# sirius1_trs80_model_2.net
KiCad netlist of a schematic drawn in EAGLE
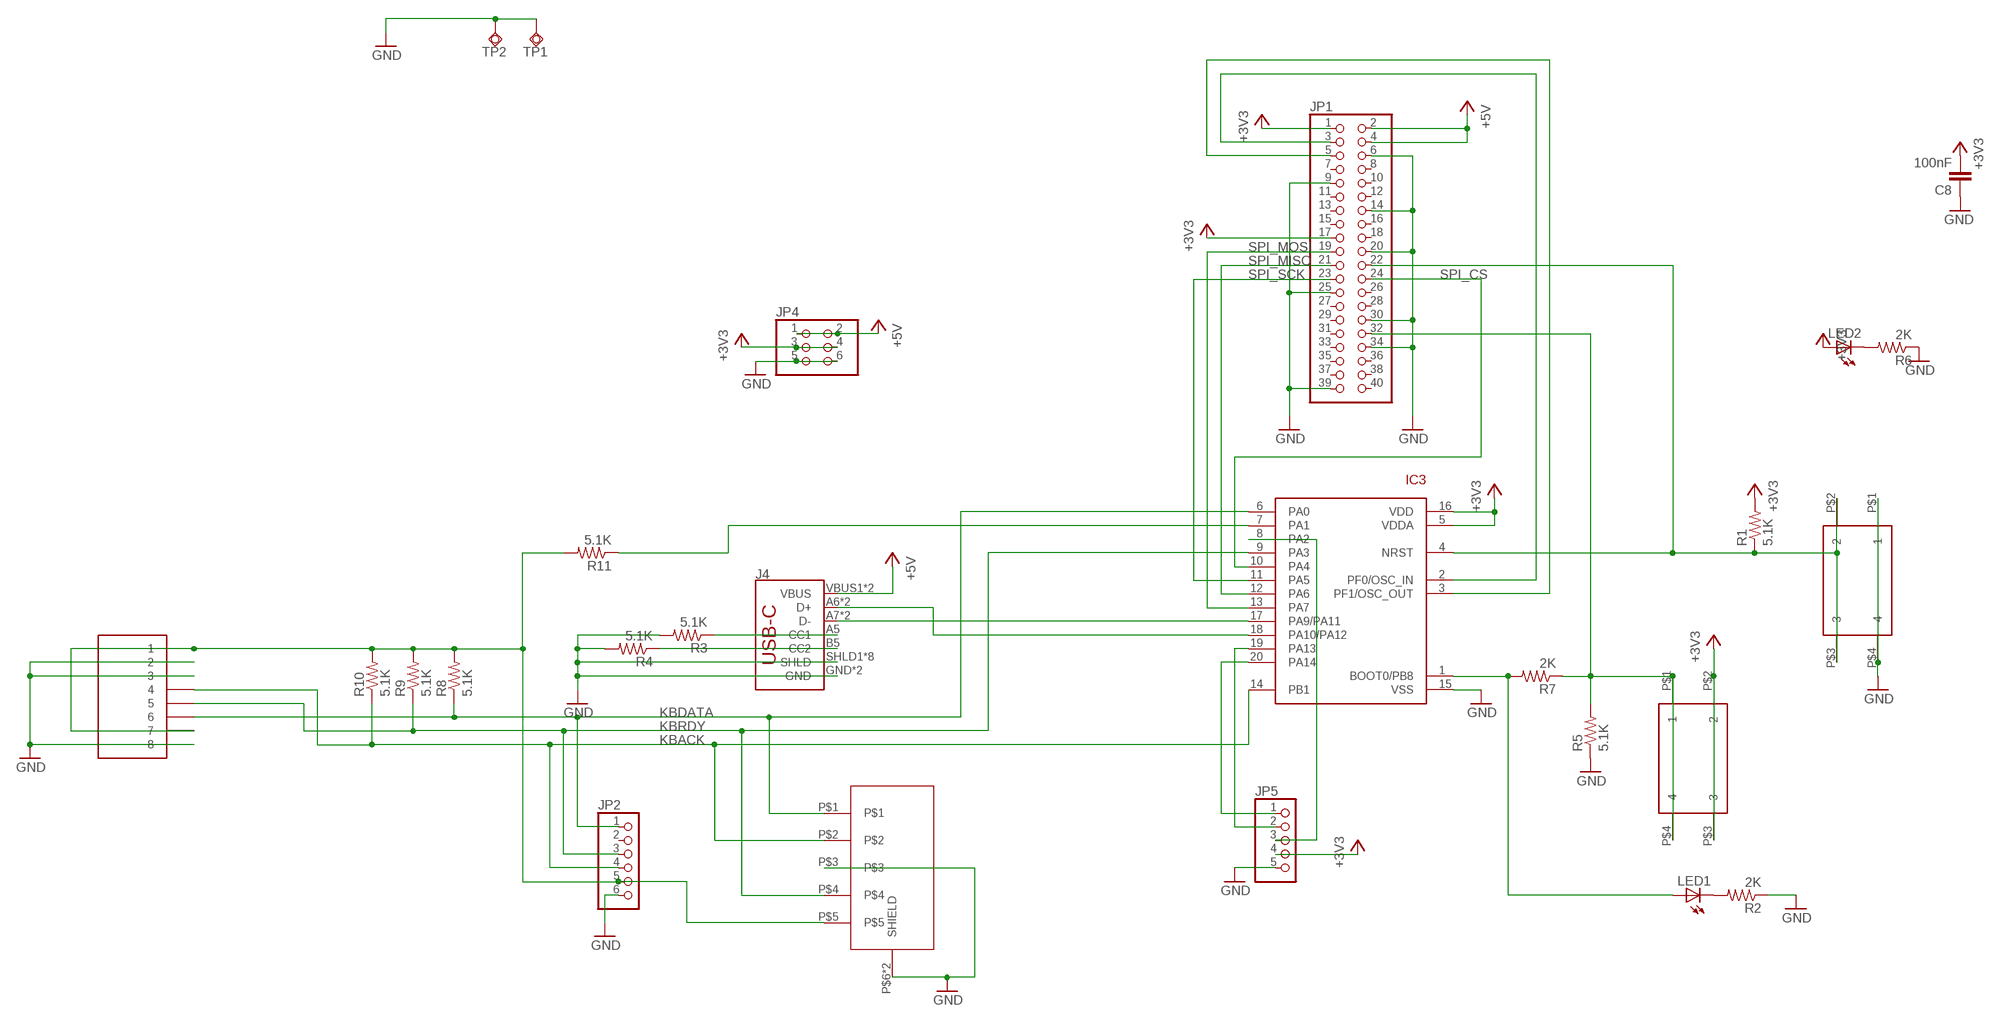
[diagram p0: schematic, sheet 1, part 1 of 2]
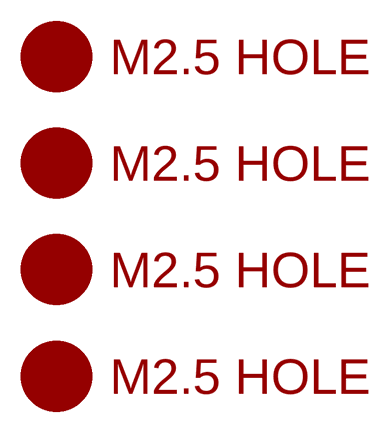
[diagram p1: schematic, sheet 1, part 2 of 2]

(export (version "E")
  (design (tool "Eeschema 10.0.6"))
  (components
    (comp (ref "C8")
      (value "100nF")
      (footprint "eagle-import:0805@1")
      (libsource (lib "eagle-import") (part "CAP0805"))
    )
    (comp (ref "IC3")
      (value "STM32F042F4")
      (footprint "eagle-import:TSSOP20")
      (libsource (lib "eagle-import") (part "STM32F042F4"))
    )
    (comp (ref "J4")
      (value "USB_C16PIN")
      (footprint "eagle-import:USB-C-16P")
      (libsource (lib "eagle-import") (part "USB_C16PIN"))
    )
    (comp (ref "JP1")
      (value "PINHD-2X20-BIG")
      (footprint "eagle-import:2X20-BIG")
      (libsource (lib "eagle-import") (part "PINHD-2X20-BIG"))
    )
    (comp (ref "JP2")
      (value "PINHD-1X6")
      (footprint "eagle-import:1X06")
      (libsource (lib "eagle-import") (part "PINHD-1X6"))
    )
    (comp (ref "JP4")
      (value "PINHD-2X3")
      (footprint "eagle-import:2X03")
      (libsource (lib "eagle-import") (part "PINHD-2X3"))
    )
    (comp (ref "JP5")
      (value "PINHD-1X5")
      (footprint "eagle-import:1X05")
      (libsource (lib "eagle-import") (part "PINHD-1X5"))
    )
    (comp (ref "LED1")
      (value "LEDCHIP-LED0805")
      (footprint "eagle-import:CHIP-LED0805")
      (libsource (lib "eagle-import") (part "LEDCHIP-LED0805"))
    )
    (comp (ref "LED2")
      (value "LEDCHIP-LED0805")
      (footprint "eagle-import:CHIP-LED0805")
      (libsource (lib "eagle-import") (part "LEDCHIP-LED0805"))
    )
    (comp (ref "R1")
      (value "5.1K")
      (footprint "eagle-import:0805")
      (libsource (lib "eagle-import") (part "RESISTOR0805-RES"))
    )
    (comp (ref "R2")
      (value "2K")
      (footprint "eagle-import:0805")
      (libsource (lib "eagle-import") (part "RESISTOR0805-RES"))
    )
    (comp (ref "R3")
      (value "5.1K")
      (footprint "eagle-import:0805")
      (libsource (lib "eagle-import") (part "RESISTOR0805-RES"))
    )
    (comp (ref "R4")
      (value "5.1K")
      (footprint "eagle-import:0805")
      (libsource (lib "eagle-import") (part "RESISTOR0805-RES"))
    )
    (comp (ref "R5")
      (value "5.1K")
      (footprint "eagle-import:0805")
      (libsource (lib "eagle-import") (part "RESISTOR0805-RES"))
    )
    (comp (ref "R6")
      (value "2K")
      (footprint "eagle-import:0805")
      (libsource (lib "eagle-import") (part "RESISTOR0805-RES"))
    )
    (comp (ref "R7")
      (value "2K")
      (footprint "eagle-import:0805")
      (libsource (lib "eagle-import") (part "RESISTOR0805-RES"))
    )
    (comp (ref "R8")
      (value "5.1K")
      (footprint "eagle-import:0805")
      (libsource (lib "eagle-import") (part "RESISTOR0805-RES"))
    )
    (comp (ref "R9")
      (value "5.1K")
      (footprint "eagle-import:0805")
      (libsource (lib "eagle-import") (part "RESISTOR0805-RES"))
    )
    (comp (ref "R10")
      (value "5.1K")
      (footprint "eagle-import:0805")
      (libsource (lib "eagle-import") (part "RESISTOR0805-RES"))
    )
    (comp (ref "R11")
      (value "5.1K")
      (footprint "eagle-import:0805")
      (libsource (lib "eagle-import") (part "RESISTOR0805-RES"))
    )
    (comp (ref "SW1")
      (value "324_SW")
      (footprint "eagle-import:342_SWICH_FOOT")
      (libsource (lib "eagle-import") (part "324_SW"))
    )
    (comp (ref "SW4")
      (value "324_SW")
      (footprint "eagle-import:342_SWICH_FOOT")
      (libsource (lib "eagle-import") (part "324_SW"))
    )
    (comp (ref "TP1")
      (value "TPSQPAD1-17")
      (footprint "eagle-import:P1-17")
      (libsource (lib "eagle-import") (part "TPSQPAD1-17"))
    )
    (comp (ref "TP2")
      (value "TPSQPAD1-17")
      (footprint "eagle-import:P1-17")
      (libsource (lib "eagle-import") (part "TPSQPAD1-17"))
    )
    (comp (ref "U$1")
      (value "DIN5")
      (footprint "eagle-import:DIN5")
      (libsource (lib "eagle-import") (part "DIN5"))
    )
    (comp (ref "U$2")
      (value "M2.5HOLE")
      (footprint "eagle-import:M2.5HOLE")
      (libsource (lib "eagle-import") (part "M2.5HOLE"))
    )
    (comp (ref "U$3")
      (value "M2.5HOLE")
      (footprint "eagle-import:M2.5HOLE")
      (libsource (lib "eagle-import") (part "M2.5HOLE"))
    )
    (comp (ref "U$4")
      (value "M2.5HOLE")
      (footprint "eagle-import:M2.5HOLE")
      (libsource (lib "eagle-import") (part "M2.5HOLE"))
    )
    (comp (ref "U$5")
      (value "M2.5HOLE")
      (footprint "eagle-import:M2.5HOLE")
      (libsource (lib "eagle-import") (part "M2.5HOLE"))
    )
    (comp (ref "U1")
      (value "RJ45")
      (footprint "eagle-import:RJ45-8")
      (libsource (lib "eagle-import") (part "RJ45-8PTH"))
    )
  )
  (nets
    (net (code "1") (name "+3V3") (class "Default")
      (node (ref "C8") (pin "2") (pinfunction "2_2") (pintype "passive"))
      (node (ref "IC3") (pin "16") (pinfunction "VDD_16") (pintype "bidirectional"))
      (node (ref "IC3") (pin "5") (pinfunction "VDDA_5") (pintype "bidirectional"))
      (node (ref "JP1") (pin "1") (pinfunction "1_1") (pintype "passive"))
      (node (ref "JP1") (pin "17") (pinfunction "17_17") (pintype "passive"))
      (node (ref "JP4") (pin "3") (pinfunction "3_3") (pintype "passive"))
      (node (ref "JP4") (pin "4") (pinfunction "4_4") (pintype "passive"))
      (node (ref "JP5") (pin "4") (pinfunction "4_4") (pintype "passive"))
      (node (ref "LED2") (pin "A") (pinfunction "A_A") (pintype "passive"))
      (node (ref "R1") (pin "2") (pinfunction "2_2") (pintype "passive"))
      (node (ref "SW1") (pin "P$2") (pinfunction "2_P$2") (pintype "bidirectional"))
      (node (ref "SW1") (pin "P$3") (pinfunction "3_P$3") (pintype "bidirectional"))
    )
    (net (code "2") (name "+5V") (class "Default")
      (node (ref "J4") (pin "VBUS1") (pinfunction "VBUS_VBUS1") (pintype "bidirectional"))
      (node (ref "J4") (pin "VBUS2") (pinfunction "VBUS_VBUS2") (pintype "bidirectional"))
      (node (ref "JP1") (pin "2") (pinfunction "2_2") (pintype "passive"))
      (node (ref "JP1") (pin "4") (pinfunction "4_4") (pintype "passive"))
      (node (ref "JP4") (pin "1") (pinfunction "1_1") (pintype "passive"))
      (node (ref "JP4") (pin "2") (pinfunction "2_2") (pintype "passive"))
    )
    (net (code "3") (name "/KBACK") (class "Default")
      (node (ref "IC3") (pin "14") (pinfunction "PB1_14") (pintype "bidirectional"))
      (node (ref "JP2") (pin "4") (pinfunction "4_4") (pintype "passive"))
      (node (ref "R10") (pin "1") (pinfunction "1_1") (pintype "passive"))
      (node (ref "U$1") (pin "P$2") (pinfunction "P$2_P$2") (pintype "bidirectional"))
      (node (ref "U1") (pin "4") (pinfunction "4_4") (pintype "bidirectional"))
    )
    (net (code "4") (name "/KBDATA") (class "Default")
      (node (ref "IC3") (pin "6") (pinfunction "PA0_6") (pintype "bidirectional"))
      (node (ref "JP2") (pin "1") (pinfunction "1_1") (pintype "passive"))
      (node (ref "R8") (pin "1") (pinfunction "1_1") (pintype "passive"))
      (node (ref "U$1") (pin "P$1") (pinfunction "P$1_P$1") (pintype "bidirectional"))
      (node (ref "U1") (pin "6") (pinfunction "6_6") (pintype "bidirectional"))
    )
    (net (code "5") (name "/KBRDY") (class "Default")
      (node (ref "IC3") (pin "9") (pinfunction "PA3_9") (pintype "bidirectional"))
      (node (ref "JP2") (pin "3") (pinfunction "3_3") (pintype "passive"))
      (node (ref "R9") (pin "1") (pinfunction "1_1") (pintype "passive"))
      (node (ref "U$1") (pin "P$4") (pinfunction "P$4_P$4") (pintype "bidirectional"))
      (node (ref "U1") (pin "5") (pinfunction "5_5") (pintype "bidirectional"))
    )
    (net (code "6") (name "/SPI_CS") (class "Default")
      (node (ref "IC3") (pin "10") (pinfunction "PA4_10") (pintype "bidirectional"))
      (node (ref "JP1") (pin "24") (pinfunction "24_24") (pintype "passive"))
    )
    (net (code "7") (name "/SPI_MISO") (class "Default")
      (node (ref "IC3") (pin "12") (pinfunction "PA6_12") (pintype "bidirectional"))
      (node (ref "JP1") (pin "21") (pinfunction "21_21") (pintype "passive"))
    )
    (net (code "8") (name "/SPI_MOSI") (class "Default")
      (node (ref "IC3") (pin "13") (pinfunction "PA7_13") (pintype "bidirectional"))
      (node (ref "JP1") (pin "19") (pinfunction "19_19") (pintype "passive"))
    )
    (net (code "9") (name "/SPI_SCK") (class "Default")
      (node (ref "IC3") (pin "11") (pinfunction "PA5_11") (pintype "bidirectional"))
      (node (ref "JP1") (pin "23") (pinfunction "23_23") (pintype "passive"))
    )
    (net (code "10") (name "GND") (class "Default")
      (node (ref "C8") (pin "1") (pinfunction "1_1") (pintype "passive"))
      (node (ref "IC3") (pin "15") (pinfunction "VSS_15") (pintype "bidirectional"))
      (node (ref "J4") (pin "GND") (pinfunction "GND_GND") (pintype "bidirectional"))
      (node (ref "J4") (pin "GND2") (pinfunction "GND_GND2") (pintype "bidirectional"))
      (node (ref "J4") (pin "SHLD1") (pinfunction "SHLD_SHLD1") (pintype "bidirectional"))
      (node (ref "J4") (pin "SHLD2") (pinfunction "SHLD_SHLD2") (pintype "bidirectional"))
      (node (ref "J4") (pin "SHLD3") (pinfunction "SHLD_SHLD3") (pintype "bidirectional"))
      (node (ref "J4") (pin "SHLD4") (pinfunction "SHLD_SHLD4") (pintype "bidirectional"))
      (node (ref "J4") (pin "SHLD5") (pinfunction "SHLD_SHLD5") (pintype "bidirectional"))
      (node (ref "J4") (pin "SHLD6") (pinfunction "SHLD_SHLD6") (pintype "bidirectional"))
      (node (ref "J4") (pin "SHLD7") (pinfunction "SHLD_SHLD7") (pintype "bidirectional"))
      (node (ref "J4") (pin "SHLD8") (pinfunction "SHLD_SHLD8") (pintype "bidirectional"))
      (node (ref "JP1") (pin "14") (pinfunction "14_14") (pintype "passive"))
      (node (ref "JP1") (pin "20") (pinfunction "20_20") (pintype "passive"))
      (node (ref "JP1") (pin "25") (pinfunction "25_25") (pintype "passive"))
      (node (ref "JP1") (pin "30") (pinfunction "30_30") (pintype "passive"))
      (node (ref "JP1") (pin "34") (pinfunction "34_34") (pintype "passive"))
      (node (ref "JP1") (pin "39") (pinfunction "39_39") (pintype "passive"))
      (node (ref "JP1") (pin "6") (pinfunction "6_6") (pintype "passive"))
      (node (ref "JP1") (pin "9") (pinfunction "9_9") (pintype "passive"))
      (node (ref "JP2") (pin "6") (pinfunction "6_6") (pintype "passive"))
      (node (ref "JP4") (pin "5") (pinfunction "5_5") (pintype "passive"))
      (node (ref "JP4") (pin "6") (pinfunction "6_6") (pintype "passive"))
      (node (ref "JP5") (pin "5") (pinfunction "5_5") (pintype "passive"))
      (node (ref "R2") (pin "1") (pinfunction "1_1") (pintype "passive"))
      (node (ref "R3") (pin "2") (pinfunction "2_2") (pintype "passive"))
      (node (ref "R4") (pin "2") (pinfunction "2_2") (pintype "passive"))
      (node (ref "R5") (pin "1") (pinfunction "1_1") (pintype "passive"))
      (node (ref "R6") (pin "1") (pinfunction "1_1") (pintype "passive"))
      (node (ref "SW4") (pin "P$1") (pinfunction "1_P$1") (pintype "bidirectional"))
      (node (ref "SW4") (pin "P$4") (pinfunction "4_P$4") (pintype "bidirectional"))
      (node (ref "TP1") (pin "TP") (pinfunction "TP_TP") (pintype "input"))
      (node (ref "TP2") (pin "TP") (pinfunction "TP_TP") (pintype "input"))
      (node (ref "U$1") (pin "P$3") (pinfunction "P$3_P$3") (pintype "bidirectional"))
      (node (ref "U$1") (pin "P$6") (pinfunction "SHIELD_P$6") (pintype "bidirectional"))
      (node (ref "U$1") (pin "P$7") (pinfunction "SHIELD_P$7") (pintype "bidirectional"))
      (node (ref "U1") (pin "2") (pinfunction "2_2") (pintype "bidirectional"))
      (node (ref "U1") (pin "3") (pinfunction "3_3") (pintype "bidirectional"))
      (node (ref "U1") (pin "8") (pinfunction "8_8") (pintype "bidirectional"))
    )
    (net (code "11") (name "Net-(IC3-BOOT0{slash}PB8)") (class "Default")
      (node (ref "IC3") (pin "1") (pinfunction "BOOT0/PB8_1") (pintype "bidirectional"))
      (node (ref "LED1") (pin "A") (pinfunction "A_A") (pintype "passive"))
      (node (ref "R7") (pin "2") (pinfunction "2_2") (pintype "passive"))
    )
    (net (code "12") (name "Net-(IC3-NRST)") (class "Default")
      (node (ref "IC3") (pin "4") (pinfunction "NRST_4") (pintype "bidirectional"))
      (node (ref "JP1") (pin "22") (pinfunction "22_22") (pintype "passive"))
      (node (ref "R1") (pin "1") (pinfunction "1_1") (pintype "passive"))
      (node (ref "SW4") (pin "P$2") (pinfunction "2_P$2") (pintype "bidirectional"))
      (node (ref "SW4") (pin "P$3") (pinfunction "3_P$3") (pintype "bidirectional"))
    )
    (net (code "13") (name "Net-(IC3-PA1)") (class "Default")
      (node (ref "IC3") (pin "7") (pinfunction "PA1_7") (pintype "bidirectional"))
      (node (ref "R11") (pin "1") (pinfunction "1_1") (pintype "passive"))
    )
    (net (code "14") (name "Net-(IC3-PA2)") (class "Default")
      (node (ref "IC3") (pin "8") (pinfunction "PA2_8") (pintype "bidirectional"))
      (node (ref "JP5") (pin "3") (pinfunction "3_3") (pintype "passive"))
    )
    (net (code "15") (name "Net-(IC3-PA9{slash}PA11)") (class "Default")
      (node (ref "IC3") (pin "17") (pinfunction "PA9/PA11_17") (pintype "bidirectional"))
      (node (ref "J4") (pin "A7") (pinfunction "D-_A7") (pintype "bidirectional"))
      (node (ref "J4") (pin "B7") (pinfunction "D-_B7") (pintype "bidirectional"))
    )
    (net (code "16") (name "Net-(IC3-PA10{slash}PA12)") (class "Default")
      (node (ref "IC3") (pin "18") (pinfunction "PA10/PA12_18") (pintype "bidirectional"))
      (node (ref "J4") (pin "A6") (pinfunction "D+_A6") (pintype "bidirectional"))
      (node (ref "J4") (pin "B6") (pinfunction "D+_B6") (pintype "bidirectional"))
    )
    (net (code "17") (name "Net-(IC3-PA13)") (class "Default")
      (node (ref "IC3") (pin "19") (pinfunction "PA13_19") (pintype "bidirectional"))
      (node (ref "JP5") (pin "2") (pinfunction "2_2") (pintype "passive"))
    )
    (net (code "18") (name "Net-(IC3-PA14)") (class "Default")
      (node (ref "IC3") (pin "20") (pinfunction "PA14_20") (pintype "bidirectional"))
      (node (ref "JP5") (pin "1") (pinfunction "1_1") (pintype "passive"))
    )
    (net (code "19") (name "Net-(IC3-PF0{slash}OSC_IN)") (class "Default")
      (node (ref "IC3") (pin "2") (pinfunction "PF0/OSC_IN_2") (pintype "bidirectional"))
      (node (ref "JP1") (pin "3") (pinfunction "3_3") (pintype "passive"))
    )
    (net (code "20") (name "Net-(IC3-PF1{slash}OSC_OUT)") (class "Default")
      (node (ref "IC3") (pin "3") (pinfunction "PF1/OSC_OUT_3") (pintype "bidirectional"))
      (node (ref "JP1") (pin "5") (pinfunction "5_5") (pintype "passive"))
    )
    (net (code "21") (name "Net-(J4-CC1)") (class "Default")
      (node (ref "J4") (pin "A5") (pinfunction "CC1_A5") (pintype "bidirectional"))
      (node (ref "R3") (pin "1") (pinfunction "1_1") (pintype "passive"))
    )
    (net (code "22") (name "Net-(J4-CC2)") (class "Default")
      (node (ref "J4") (pin "B5") (pinfunction "CC2_B5") (pintype "bidirectional"))
      (node (ref "R4") (pin "1") (pinfunction "1_1") (pintype "passive"))
    )
    (net (code "23") (name "Net-(JP2-Pad5)") (class "Default")
      (node (ref "JP2") (pin "5") (pinfunction "5_5") (pintype "passive"))
      (node (ref "R10") (pin "2") (pinfunction "2_2") (pintype "passive"))
      (node (ref "R11") (pin "2") (pinfunction "2_2") (pintype "passive"))
      (node (ref "R8") (pin "2") (pinfunction "2_2") (pintype "passive"))
      (node (ref "R9") (pin "2") (pinfunction "2_2") (pintype "passive"))
      (node (ref "U$1") (pin "P$5") (pinfunction "P$5_P$5") (pintype "bidirectional"))
      (node (ref "U1") (pin "1") (pinfunction "1_1") (pintype "bidirectional"))
      (node (ref "U1") (pin "7") (pinfunction "7_7") (pintype "bidirectional"))
    )
    (net (code "24") (name "Net-(LED1-PadC)") (class "Default")
      (node (ref "LED1") (pin "C") (pinfunction "C_C") (pintype "passive"))
      (node (ref "R2") (pin "2") (pinfunction "2_2") (pintype "passive"))
    )
    (net (code "25") (name "Net-(LED2-PadC)") (class "Default")
      (node (ref "LED2") (pin "C") (pinfunction "C_C") (pintype "passive"))
      (node (ref "R6") (pin "2") (pinfunction "2_2") (pintype "passive"))
    )
    (net (code "26") (name "Net-(SW1-1)") (class "Default")
      (node (ref "JP1") (pin "32") (pinfunction "32_32") (pintype "passive"))
      (node (ref "R5") (pin "2") (pinfunction "2_2") (pintype "passive"))
      (node (ref "R7") (pin "1") (pinfunction "1_1") (pintype "passive"))
      (node (ref "SW1") (pin "P$1") (pinfunction "1_P$1") (pintype "bidirectional"))
      (node (ref "SW1") (pin "P$4") (pinfunction "4_P$4") (pintype "bidirectional"))
    )
    (net (code "27") (name "unconnected-(JP1-Pad7)") (class "Default")
      (node (ref "JP1") (pin "7") (pinfunction "7_7") (pintype "passive"))
    )
    (net (code "28") (name "unconnected-(JP1-Pad8)") (class "Default")
      (node (ref "JP1") (pin "8") (pinfunction "8_8") (pintype "passive"))
    )
    (net (code "29") (name "unconnected-(JP1-Pad10)") (class "Default")
      (node (ref "JP1") (pin "10") (pinfunction "10_10") (pintype "passive"))
    )
    (net (code "30") (name "unconnected-(JP1-Pad11)") (class "Default")
      (node (ref "JP1") (pin "11") (pinfunction "11_11") (pintype "passive"))
    )
    (net (code "31") (name "unconnected-(JP1-Pad12)") (class "Default")
      (node (ref "JP1") (pin "12") (pinfunction "12_12") (pintype "passive"))
    )
    (net (code "32") (name "unconnected-(JP1-Pad13)") (class "Default")
      (node (ref "JP1") (pin "13") (pinfunction "13_13") (pintype "passive"))
    )
    (net (code "33") (name "unconnected-(JP1-Pad15)") (class "Default")
      (node (ref "JP1") (pin "15") (pinfunction "15_15") (pintype "passive"))
    )
    (net (code "34") (name "unconnected-(JP1-Pad16)") (class "Default")
      (node (ref "JP1") (pin "16") (pinfunction "16_16") (pintype "passive"))
    )
    (net (code "35") (name "unconnected-(JP1-Pad18)") (class "Default")
      (node (ref "JP1") (pin "18") (pinfunction "18_18") (pintype "passive"))
    )
    (net (code "36") (name "unconnected-(JP1-Pad26)") (class "Default")
      (node (ref "JP1") (pin "26") (pinfunction "26_26") (pintype "passive"))
    )
    (net (code "37") (name "unconnected-(JP1-Pad27)") (class "Default")
      (node (ref "JP1") (pin "27") (pinfunction "27_27") (pintype "passive"))
    )
    (net (code "38") (name "unconnected-(JP1-Pad28)") (class "Default")
      (node (ref "JP1") (pin "28") (pinfunction "28_28") (pintype "passive"))
    )
    (net (code "39") (name "unconnected-(JP1-Pad29)") (class "Default")
      (node (ref "JP1") (pin "29") (pinfunction "29_29") (pintype "passive"))
    )
    (net (code "40") (name "unconnected-(JP1-Pad31)") (class "Default")
      (node (ref "JP1") (pin "31") (pinfunction "31_31") (pintype "passive"))
    )
    (net (code "41") (name "unconnected-(JP1-Pad33)") (class "Default")
      (node (ref "JP1") (pin "33") (pinfunction "33_33") (pintype "passive"))
    )
    (net (code "42") (name "unconnected-(JP1-Pad35)") (class "Default")
      (node (ref "JP1") (pin "35") (pinfunction "35_35") (pintype "passive"))
    )
    (net (code "43") (name "unconnected-(JP1-Pad36)") (class "Default")
      (node (ref "JP1") (pin "36") (pinfunction "36_36") (pintype "passive"))
    )
    (net (code "44") (name "unconnected-(JP1-Pad37)") (class "Default")
      (node (ref "JP1") (pin "37") (pinfunction "37_37") (pintype "passive"))
    )
    (net (code "45") (name "unconnected-(JP1-Pad38)") (class "Default")
      (node (ref "JP1") (pin "38") (pinfunction "38_38") (pintype "passive"))
    )
    (net (code "46") (name "unconnected-(JP1-Pad40)") (class "Default")
      (node (ref "JP1") (pin "40") (pinfunction "40_40") (pintype "passive"))
    )
    (net (code "47") (name "unconnected-(JP2-Pad2)") (class "Default")
      (node (ref "JP2") (pin "2") (pinfunction "2_2") (pintype "passive"))
    )
  )
)
